# power_board.net
KiCad netlist of a schematic drawn in EAGLE
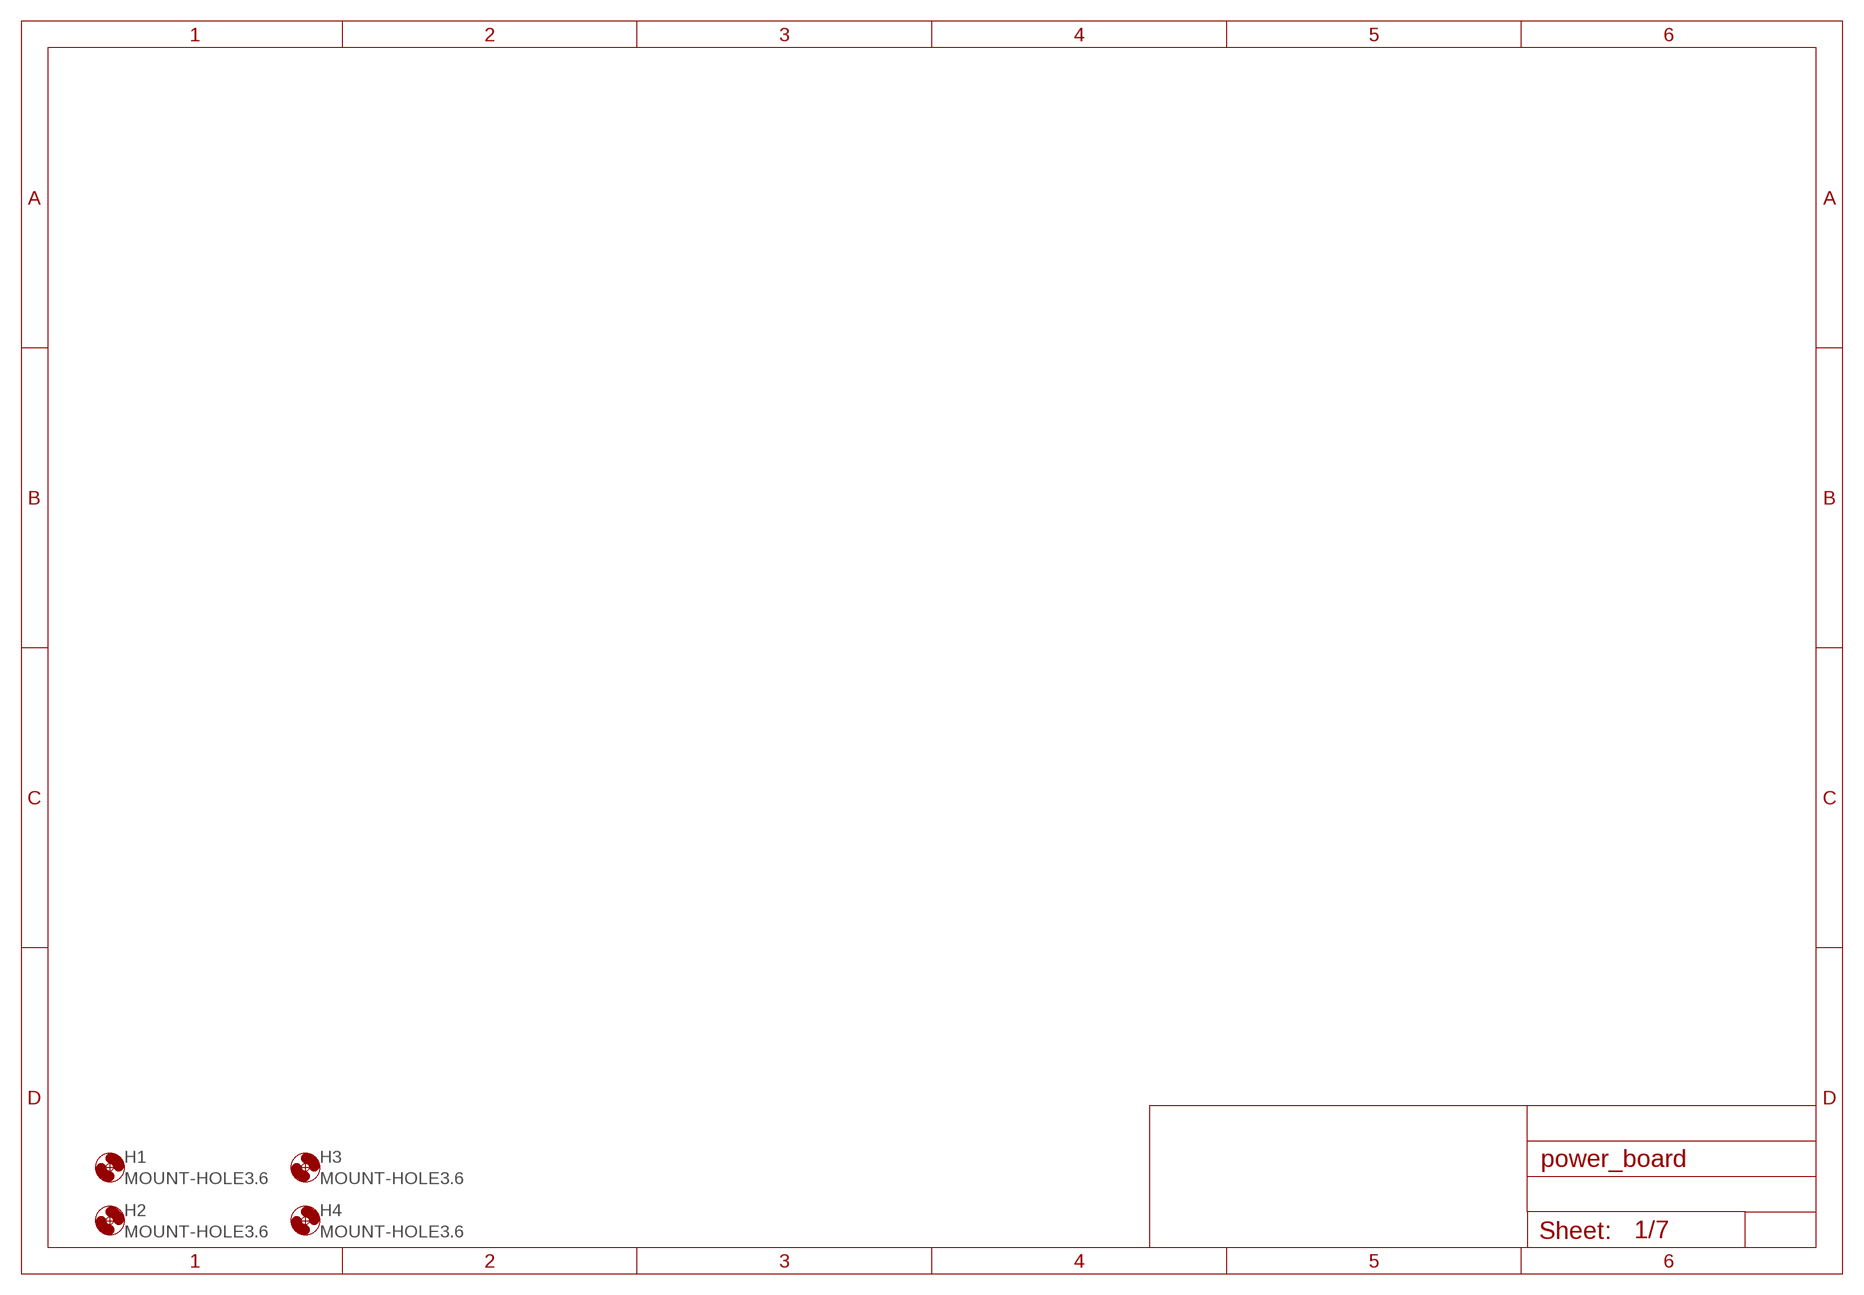
[diagram p0: schematic, sheet 1]
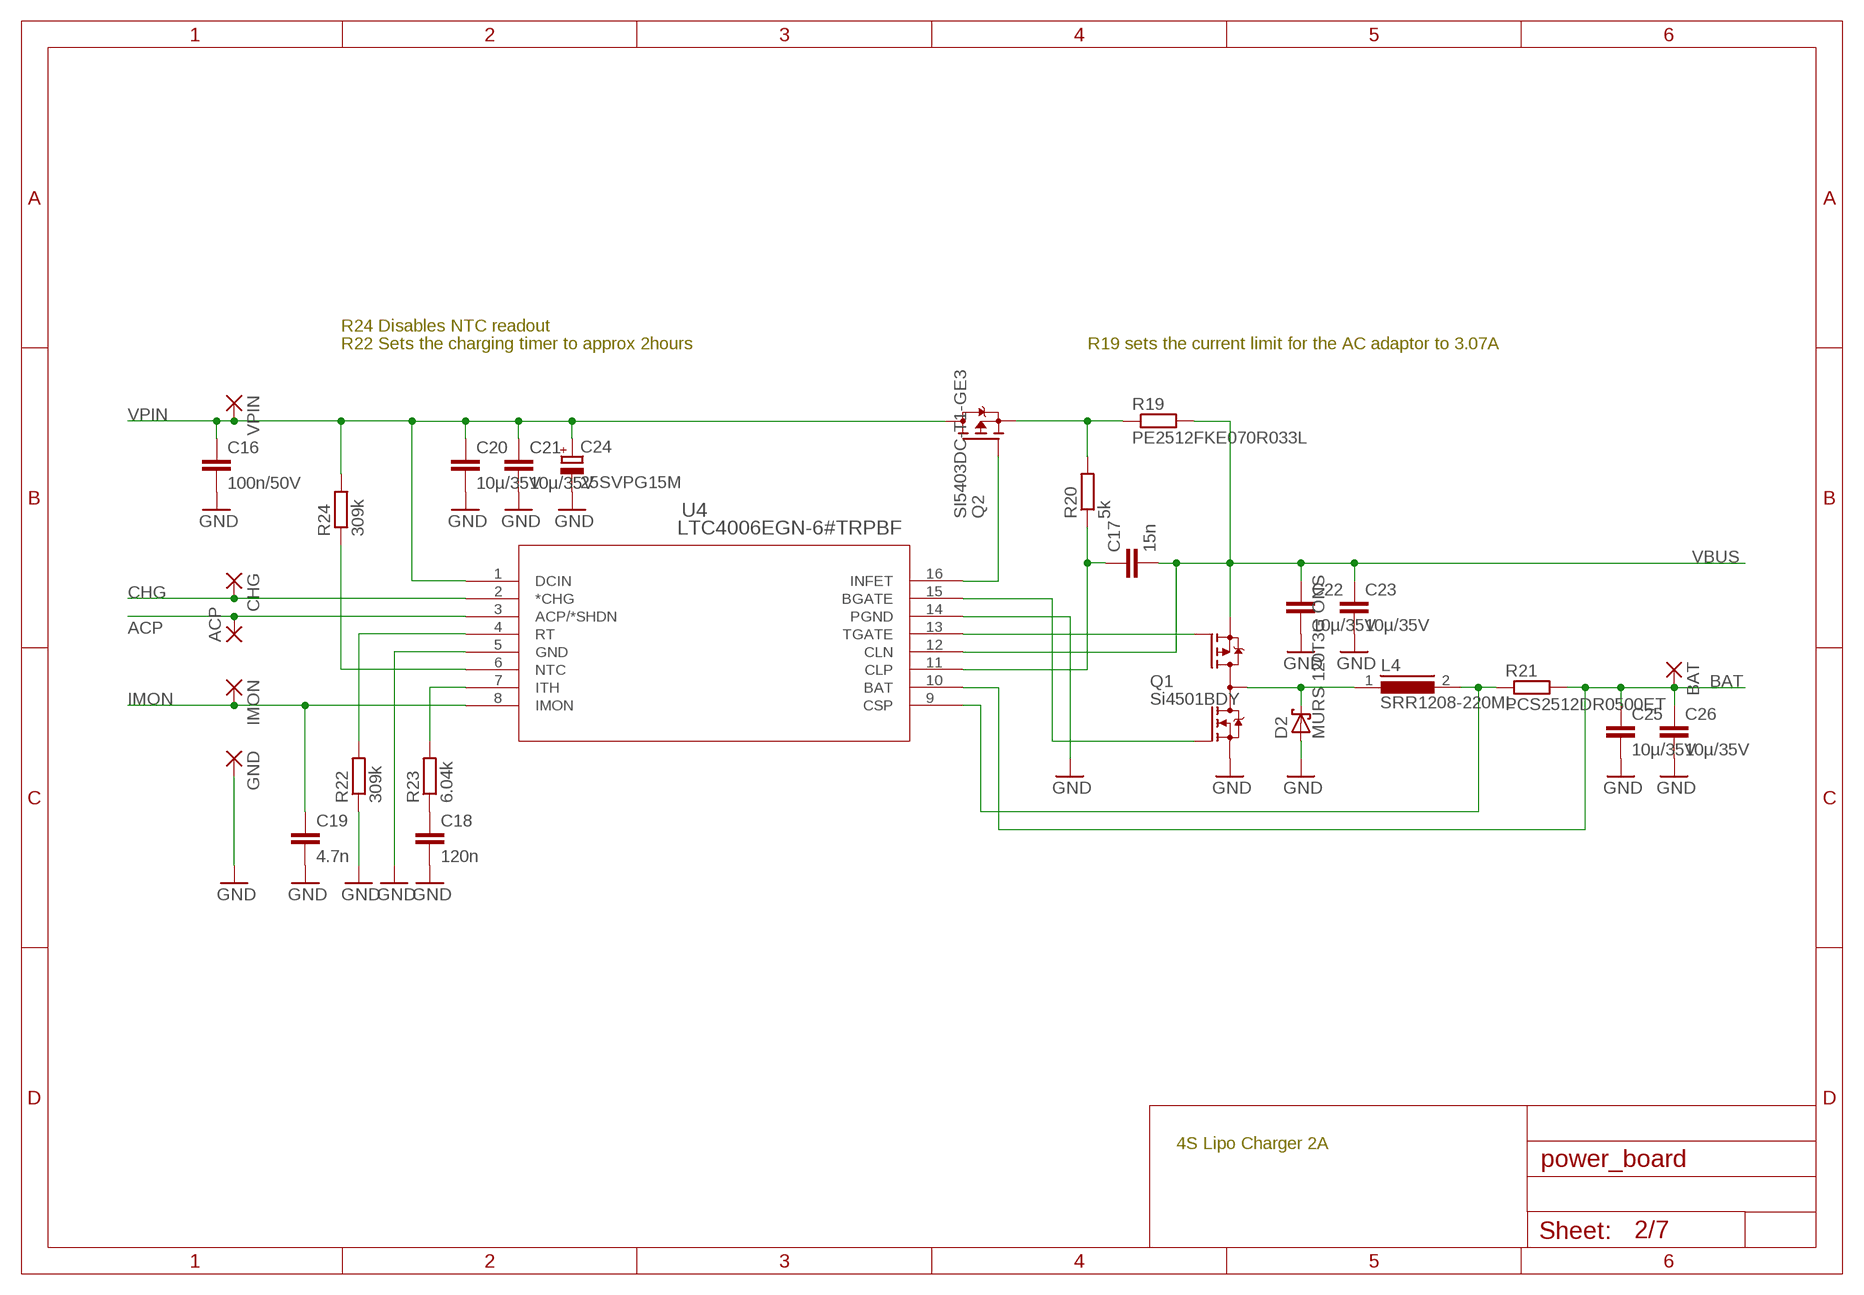
[diagram p1: schematic, sheet 2]
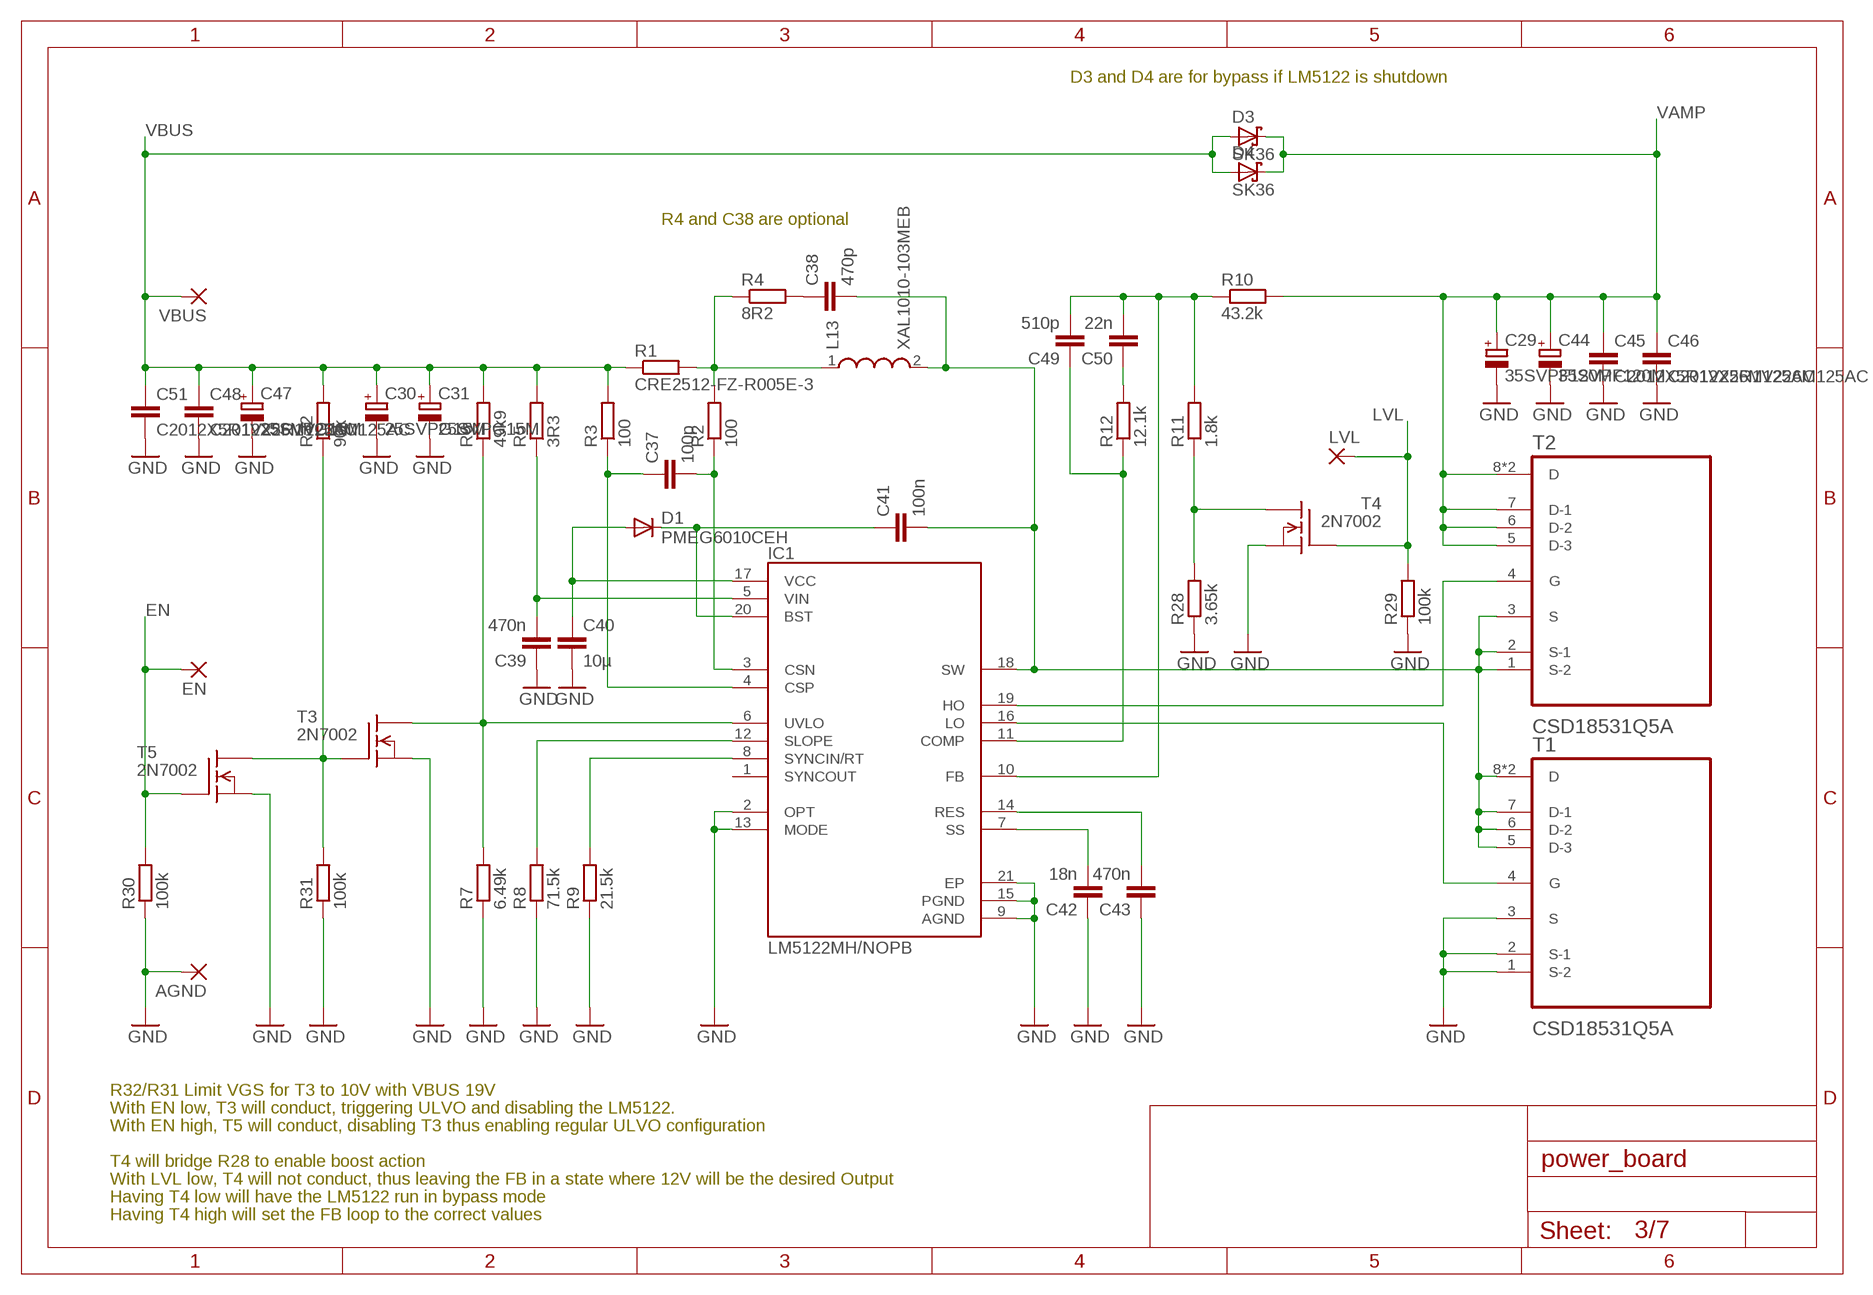
[diagram p2: schematic, sheet 3]
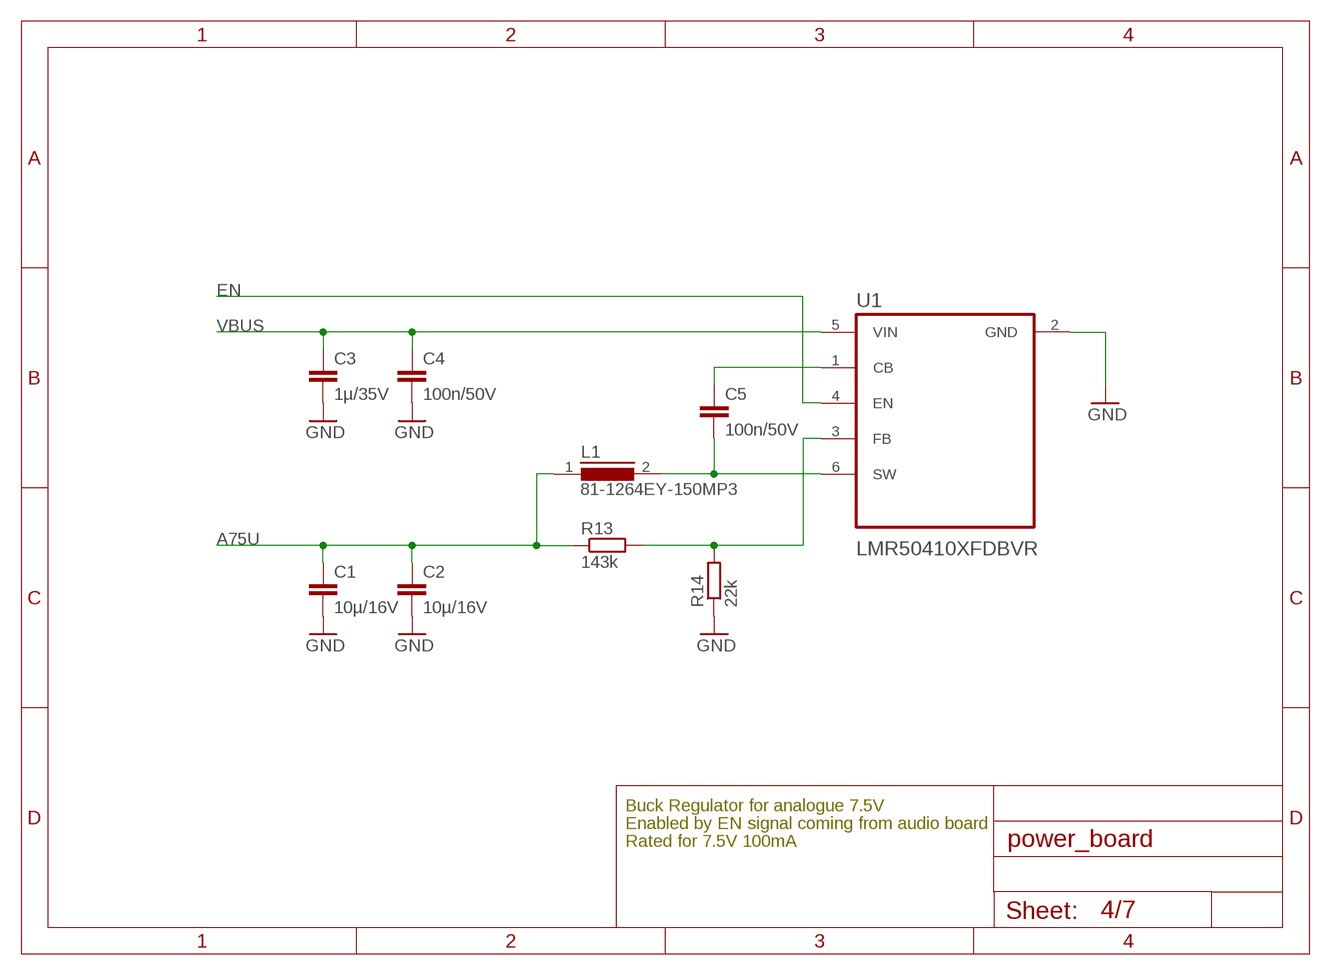
[diagram p3: schematic, sheet 4]
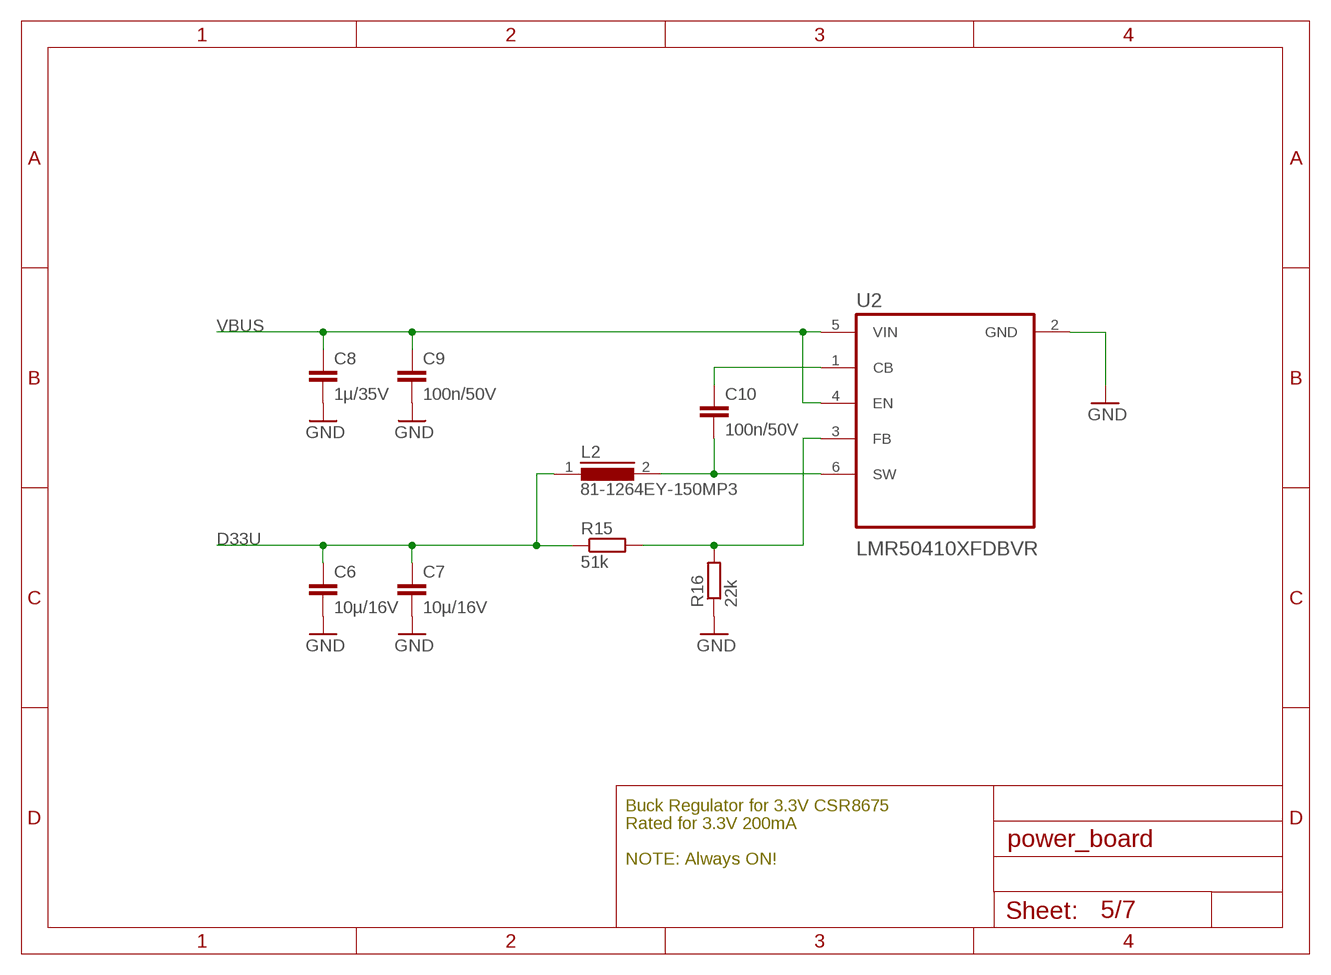
[diagram p4: schematic, sheet 5]
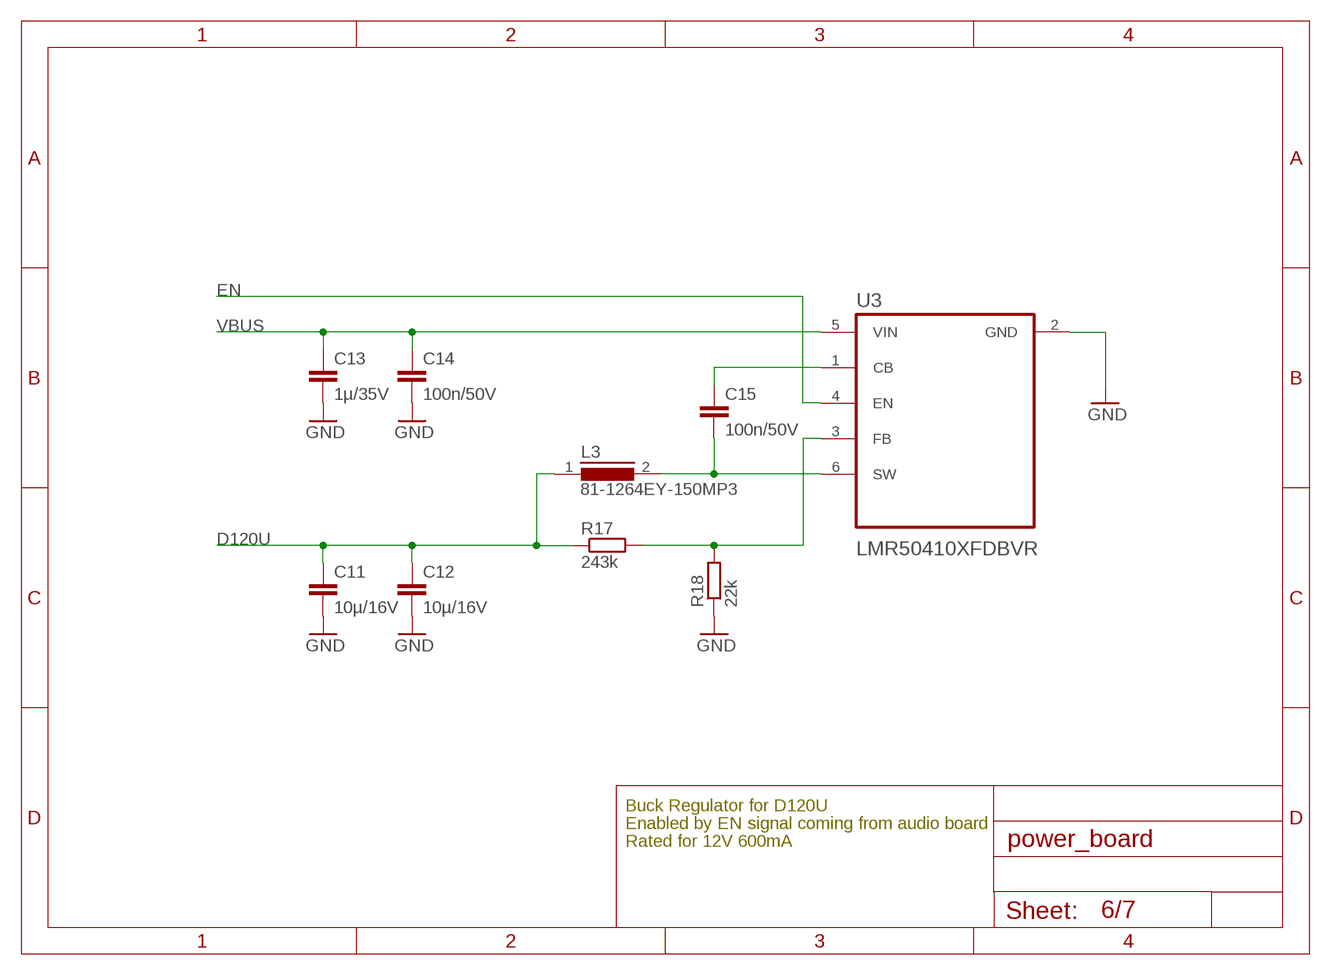
[diagram p5: schematic, sheet 6]
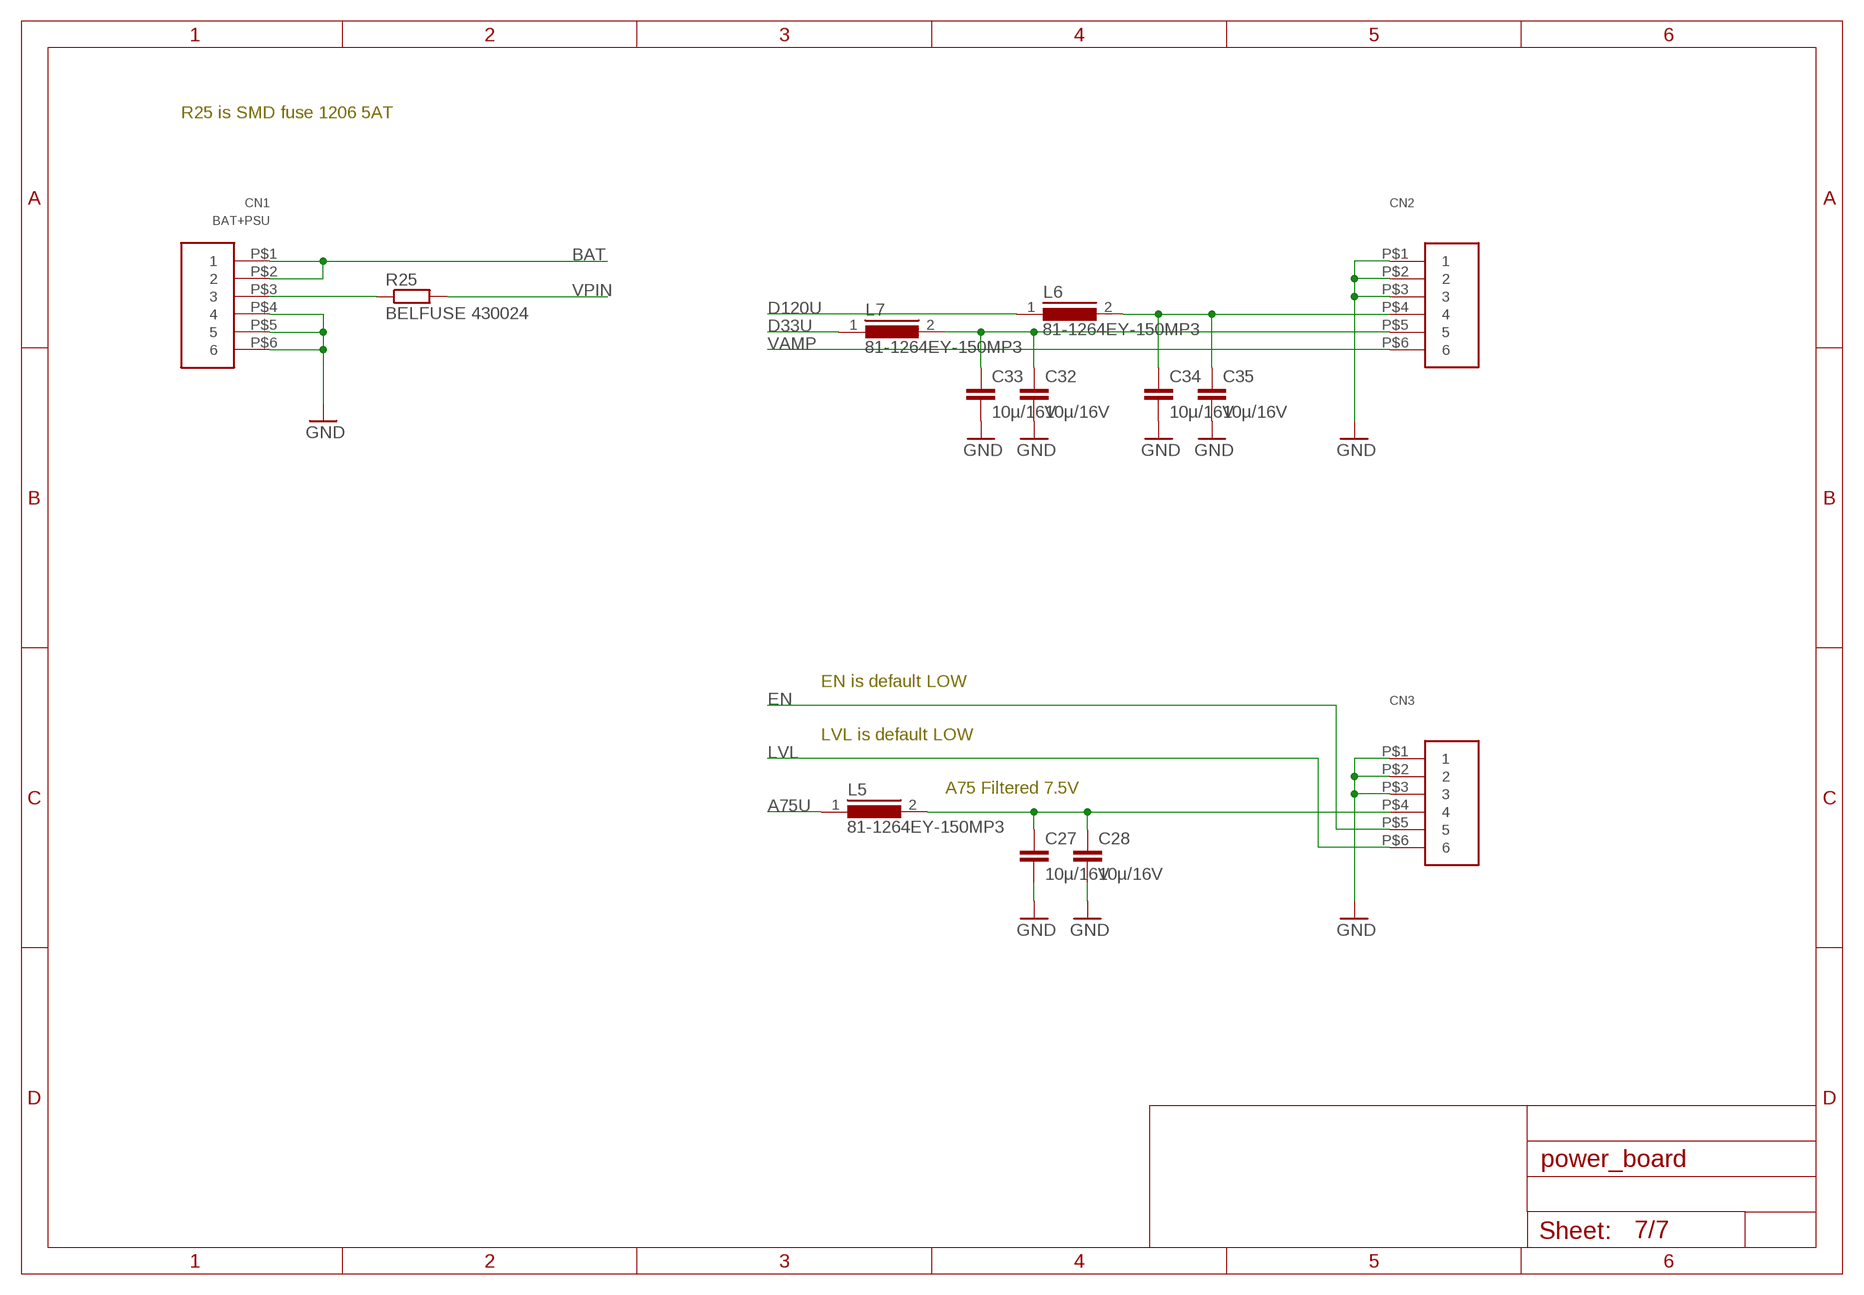
[diagram p6: schematic, sheet 7]

(export (version "E")
  (design (tool "Eeschema 10.0.6"))
  (components
    (comp (ref "H1")
      (value "MOUNT-HOLE3.6")
      (footprint "eagle-import:3,6")
      (libsource (lib "eagle-import") (part "MOUNT-HOLE3.6"))
    )
    (comp (ref "H2")
      (value "MOUNT-HOLE3.6")
      (footprint "eagle-import:3,6")
      (libsource (lib "eagle-import") (part "MOUNT-HOLE3.6"))
    )
    (comp (ref "H3")
      (value "MOUNT-HOLE3.6")
      (footprint "eagle-import:3,6")
      (libsource (lib "eagle-import") (part "MOUNT-HOLE3.6"))
    )
    (comp (ref "H4")
      (value "MOUNT-HOLE3.6")
      (footprint "eagle-import:3,6")
      (libsource (lib "eagle-import") (part "MOUNT-HOLE3.6"))
    )
    (comp (ref "C1")
      (value "10µ/16V")
      (footprint "eagle-import:C1206")
      (libsource (lib "eagle-import") (part "C-EUC1206"))
    )
    (comp (ref "C2")
      (value "10µ/16V")
      (footprint "eagle-import:C1206")
      (libsource (lib "eagle-import") (part "C-EUC1206"))
    )
    (comp (ref "C3")
      (value "1µ/35V")
      (footprint "eagle-import:C1206")
      (libsource (lib "eagle-import") (part "C-EUC1206"))
    )
    (comp (ref "C4")
      (value "100n/50V")
      (footprint "eagle-import:C1206")
      (libsource (lib "eagle-import") (part "C-EUC1206"))
    )
    (comp (ref "C5")
      (value "100n/50V")
      (footprint "eagle-import:C1206")
      (libsource (lib "eagle-import") (part "C-EUC1206"))
    )
    (comp (ref "L1")
      (value "81-1264EY-150MP3")
      (footprint "eagle-import:DR73")
      (libsource (lib "eagle-import") (part "DR73"))
    )
    (comp (ref "R13")
      (value "143k")
      (footprint "eagle-import:M0805")
      (libsource (lib "eagle-import") (part "R-EU_M0805"))
    )
    (comp (ref "R14")
      (value "22k")
      (footprint "eagle-import:M0805")
      (libsource (lib "eagle-import") (part "R-EU_M0805"))
    )
    (comp (ref "U1")
      (value "LMR50410XFDBVR")
      (footprint "eagle-import:SOT95P280X145-6N")
      (fields (field (name "MF") "Texas Instruments") (field (name "MP") "TPS560430YDBVT"))
      (libsource (lib "eagle-import") (part "TPS560430YDBVT"))
    )
    (comp (ref "C27")
      (value "10µ/16V")
      (footprint "eagle-import:C1206")
      (libsource (lib "eagle-import") (part "C-EUC1206"))
    )
    (comp (ref "C28")
      (value "10µ/16V")
      (footprint "eagle-import:C1206")
      (libsource (lib "eagle-import") (part "C-EUC1206"))
    )
    (comp (ref "C32")
      (value "10µ/16V")
      (footprint "eagle-import:C1206")
      (libsource (lib "eagle-import") (part "C-EUC1206"))
    )
    (comp (ref "C33")
      (value "10µ/16V")
      (footprint "eagle-import:C1206")
      (libsource (lib "eagle-import") (part "C-EUC1206"))
    )
    (comp (ref "C34")
      (value "10µ/16V")
      (footprint "eagle-import:C1206")
      (libsource (lib "eagle-import") (part "C-EUC1206"))
    )
    (comp (ref "C35")
      (value "10µ/16V")
      (footprint "eagle-import:C1206")
      (libsource (lib "eagle-import") (part "C-EUC1206"))
    )
    (comp (ref "CN1")
      (value "BAT+PSU")
      (footprint "eagle-import:5569_6P")
      (libsource (lib "eagle-import") (part "39-30-1060_BLANK"))
    )
    (comp (ref "CN2")
      (value "39-30-1060_BLANK")
      (footprint "eagle-import:5569_6P")
      (libsource (lib "eagle-import") (part "39-30-1060_BLANK"))
    )
    (comp (ref "CN3")
      (value "39-30-1060_BLANK")
      (footprint "eagle-import:5569_6P")
      (libsource (lib "eagle-import") (part "39-30-1060_BLANK"))
    )
    (comp (ref "L5")
      (value "81-1264EY-150MP3")
      (footprint "eagle-import:DR73")
      (libsource (lib "eagle-import") (part "DR73"))
    )
    (comp (ref "L6")
      (value "81-1264EY-150MP3")
      (footprint "eagle-import:DR73")
      (libsource (lib "eagle-import") (part "DR73"))
    )
    (comp (ref "L7")
      (value "81-1264EY-150MP3")
      (footprint "eagle-import:DR73")
      (libsource (lib "eagle-import") (part "DR73"))
    )
    (comp (ref "R25")
      (value "BELFUSE 430024")
      (footprint "eagle-import:R1206W")
      (libsource (lib "eagle-import") (part "R-EU_R1206W"))
    )
    (comp (ref "C6")
      (value "10µ/16V")
      (footprint "eagle-import:C1206")
      (libsource (lib "eagle-import") (part "C-EUC1206"))
    )
    (comp (ref "C7")
      (value "10µ/16V")
      (footprint "eagle-import:C1206")
      (libsource (lib "eagle-import") (part "C-EUC1206"))
    )
    (comp (ref "C8")
      (value "1µ/35V")
      (footprint "eagle-import:C1206")
      (libsource (lib "eagle-import") (part "C-EUC1206"))
    )
    (comp (ref "C9")
      (value "100n/50V")
      (footprint "eagle-import:C1206")
      (libsource (lib "eagle-import") (part "C-EUC1206"))
    )
    (comp (ref "C10")
      (value "100n/50V")
      (footprint "eagle-import:C1206")
      (libsource (lib "eagle-import") (part "C-EUC1206"))
    )
    (comp (ref "L2")
      (value "81-1264EY-150MP3")
      (footprint "eagle-import:DR73")
      (libsource (lib "eagle-import") (part "DR73"))
    )
    (comp (ref "R15")
      (value "51k")
      (footprint "eagle-import:M0805")
      (libsource (lib "eagle-import") (part "R-EU_M0805"))
    )
    (comp (ref "R16")
      (value "22k")
      (footprint "eagle-import:M0805")
      (libsource (lib "eagle-import") (part "R-EU_M0805"))
    )
    (comp (ref "U2")
      (value "LMR50410XFDBVR")
      (footprint "eagle-import:SOT95P280X145-6N")
      (fields (field (name "MF") "Texas Instruments") (field (name "MP") "TPS560430YDBVT"))
      (libsource (lib "eagle-import") (part "TPS560430YDBVT"))
    )
    (comp (ref "ACP")
      (value "SMD2")
      (footprint "eagle-import:SMD1,27-2,54")
      (libsource (lib "eagle-import") (part "SMD2"))
    )
    (comp (ref "BAT")
      (value "SMD2")
      (footprint "eagle-import:SMD1,27-2,54")
      (libsource (lib "eagle-import") (part "SMD2"))
    )
    (comp (ref "C16")
      (value "100n/50V")
      (footprint "eagle-import:C1206")
      (libsource (lib "eagle-import") (part "C-EUC1206"))
    )
    (comp (ref "C17")
      (value "15n")
      (footprint "eagle-import:C0805")
      (libsource (lib "eagle-import") (part "C-EUC0805"))
    )
    (comp (ref "C18")
      (value "120n")
      (footprint "eagle-import:C0805")
      (libsource (lib "eagle-import") (part "C-EUC0805"))
    )
    (comp (ref "C19")
      (value "4.7n")
      (footprint "eagle-import:C0805")
      (libsource (lib "eagle-import") (part "C-EUC0805"))
    )
    (comp (ref "C20")
      (value "10µ/35V")
      (footprint "eagle-import:C1206")
      (libsource (lib "eagle-import") (part "C-EUC1206"))
    )
    (comp (ref "C21")
      (value "10µ/35V")
      (footprint "eagle-import:C1206")
      (libsource (lib "eagle-import") (part "C-EUC1206"))
    )
    (comp (ref "C22")
      (value "10µ/35V")
      (footprint "eagle-import:C1206")
      (libsource (lib "eagle-import") (part "C-EUC1206"))
    )
    (comp (ref "C23")
      (value "10µ/35V")
      (footprint "eagle-import:C1206")
      (libsource (lib "eagle-import") (part "C-EUC1206"))
    )
    (comp (ref "C24")
      (value "25SVPG15M")
      (footprint "eagle-import:153CLV-0505")
      (libsource (lib "eagle-import") (part "CPOL-EU153CLV-0505"))
    )
    (comp (ref "C25")
      (value "10µ/35V")
      (footprint "eagle-import:C1206")
      (libsource (lib "eagle-import") (part "C-EUC1206"))
    )
    (comp (ref "C26")
      (value "10µ/35V")
      (footprint "eagle-import:C1206")
      (libsource (lib "eagle-import") (part "C-EUC1206"))
    )
    (comp (ref "CHG")
      (value "SMD2")
      (footprint "eagle-import:SMD1,27-2,54")
      (libsource (lib "eagle-import") (part "SMD2"))
    )
    (comp (ref "D2")
      (value "MURS 120T3G ONS")
      (footprint "eagle-import:SMB")
      (libsource (lib "eagle-import") (part "SCHOTTKY-DIODESMD"))
    )
    (comp (ref "GND")
      (value "SMD2")
      (footprint "eagle-import:SMD1,27-2,54")
      (libsource (lib "eagle-import") (part "SMD2"))
    )
    (comp (ref "IMON")
      (value "SMD2")
      (footprint "eagle-import:SMD1,27-2,54")
      (libsource (lib "eagle-import") (part "SMD2"))
    )
    (comp (ref "L4")
      (value "SRR1208-220ML")
      (footprint "eagle-import:DR127")
      (libsource (lib "eagle-import") (part "DR127"))
    )
    (comp (ref "Q1")
      (value "Si4501BDY")
      (footprint "eagle-import:SO08-IRF")
      (libsource (lib "eagle-import") (part "IRF7389"))
    )
    (comp (ref "Q2")
      (value "SI5403DC-T1-GE3")
      (footprint "eagle-import:1206-8CHIP-FET")
      (libsource (lib "eagle-import") (part "SI5403DC-T1-GE3"))
    )
    (comp (ref "R19")
      (value "PE2512FKE070R033L")
      (footprint "eagle-import:R2512")
      (libsource (lib "eagle-import") (part "R-EU_R2512"))
    )
    (comp (ref "R20")
      (value "5k")
      (footprint "eagle-import:R0805")
      (libsource (lib "eagle-import") (part "R-EU_R0805"))
    )
    (comp (ref "R21")
      (value "PCS2512DR0500ET")
      (footprint "eagle-import:R2512")
      (libsource (lib "eagle-import") (part "R-EU_R2512"))
    )
    (comp (ref "R22")
      (value "309k")
      (footprint "eagle-import:R0805")
      (libsource (lib "eagle-import") (part "R-EU_R0805"))
    )
    (comp (ref "R23")
      (value "6.04k")
      (footprint "eagle-import:R0805")
      (libsource (lib "eagle-import") (part "R-EU_R0805"))
    )
    (comp (ref "R24")
      (value "309k")
      (footprint "eagle-import:R0805")
      (libsource (lib "eagle-import") (part "R-EU_R0805"))
    )
    (comp (ref "U4")
      (value "LTC4006EGN-6#TRPBF")
      (footprint "eagle-import:SSOP-16_GN")
      (fields (field (name "MF") "Analog Devices"))
      (libsource (lib "eagle-import") (part "LTC4006EGN-6#TRPBF"))
    )
    (comp (ref "VPIN")
      (value "SMD2")
      (footprint "eagle-import:SMD1,27-2,54")
      (libsource (lib "eagle-import") (part "SMD2"))
    )
    (comp (ref "C11")
      (value "10µ/16V")
      (footprint "eagle-import:C1206")
      (libsource (lib "eagle-import") (part "C-EUC1206"))
    )
    (comp (ref "C12")
      (value "10µ/16V")
      (footprint "eagle-import:C1206")
      (libsource (lib "eagle-import") (part "C-EUC1206"))
    )
    (comp (ref "C13")
      (value "1µ/35V")
      (footprint "eagle-import:C1206")
      (libsource (lib "eagle-import") (part "C-EUC1206"))
    )
    (comp (ref "C14")
      (value "100n/50V")
      (footprint "eagle-import:C1206")
      (libsource (lib "eagle-import") (part "C-EUC1206"))
    )
    (comp (ref "C15")
      (value "100n/50V")
      (footprint "eagle-import:C1206")
      (libsource (lib "eagle-import") (part "C-EUC1206"))
    )
    (comp (ref "L3")
      (value "81-1264EY-150MP3")
      (footprint "eagle-import:DR73")
      (libsource (lib "eagle-import") (part "DR73"))
    )
    (comp (ref "R17")
      (value "243k")
      (footprint "eagle-import:M0805")
      (libsource (lib "eagle-import") (part "R-EU_M0805"))
    )
    (comp (ref "R18")
      (value "22k")
      (footprint "eagle-import:M0805")
      (libsource (lib "eagle-import") (part "R-EU_M0805"))
    )
    (comp (ref "U3")
      (value "LMR50410XFDBVR")
      (footprint "eagle-import:SOT95P280X145-6N")
      (fields (field (name "MF") "Texas Instruments") (field (name "MP") "TPS560430YDBVT"))
      (libsource (lib "eagle-import") (part "TPS560430YDBVT"))
    )
    (comp (ref "AGND")
      (value "SMD2")
      (footprint "eagle-import:SMD1,27-2,54")
      (libsource (lib "eagle-import") (part "SMD2"))
    )
    (comp (ref "C29")
      (value "35SVPF120M")
      (footprint "eagle-import:153CLV-1012")
      (libsource (lib "eagle-import") (part "CPOL-EU153CLV-1012"))
    )
    (comp (ref "C30")
      (value "25SVPG15M")
      (footprint "eagle-import:153CLV-0505")
      (libsource (lib "eagle-import") (part "CPOL-EU153CLV-0505"))
    )
    (comp (ref "C31")
      (value "25SVPG15M")
      (footprint "eagle-import:153CLV-0505")
      (libsource (lib "eagle-import") (part "CPOL-EU153CLV-0505"))
    )
    (comp (ref "C37")
      (value "100p")
      (footprint "eagle-import:C0805")
      (libsource (lib "eagle-import") (part "C-EUC0805"))
    )
    (comp (ref "C38")
      (value "470p")
      (footprint "eagle-import:C0805")
      (libsource (lib "eagle-import") (part "C-EUC0805"))
    )
    (comp (ref "C39")
      (value "470n")
      (footprint "eagle-import:C0805")
      (libsource (lib "eagle-import") (part "C-EUC0805"))
    )
    (comp (ref "C40")
      (value "10µ")
      (footprint "eagle-import:C1206")
      (libsource (lib "eagle-import") (part "C-EUC1206"))
    )
    (comp (ref "C41")
      (value "100n")
      (footprint "eagle-import:C0805")
      (libsource (lib "eagle-import") (part "C-EUC0805"))
    )
    (comp (ref "C42")
      (value "18n")
      (footprint "eagle-import:C0805")
      (libsource (lib "eagle-import") (part "C-EUC0805"))
    )
    (comp (ref "C43")
      (value "470n")
      (footprint "eagle-import:C0805")
      (libsource (lib "eagle-import") (part "C-EUC0805"))
    )
    (comp (ref "C44")
      (value "35SVPF120M")
      (footprint "eagle-import:153CLV-1012")
      (libsource (lib "eagle-import") (part "CPOL-EU153CLV-1012"))
    )
    (comp (ref "C45")
      (value "C2012X5R1V226M125AC")
      (footprint "eagle-import:C0805")
      (libsource (lib "eagle-import") (part "C-EUC0805"))
    )
    (comp (ref "C46")
      (value "C2012X5R1V226M125AC")
      (footprint "eagle-import:C0805")
      (libsource (lib "eagle-import") (part "C-EUC0805"))
    )
    (comp (ref "C47")
      (value "25SVPG15M")
      (footprint "eagle-import:153CLV-0505")
      (libsource (lib "eagle-import") (part "CPOL-EU153CLV-0505"))
    )
    (comp (ref "C48")
      (value "C2012X5R1V226M125AC")
      (footprint "eagle-import:C0805")
      (libsource (lib "eagle-import") (part "C-EUC0805"))
    )
    (comp (ref "C49")
      (value "510p")
      (footprint "eagle-import:C0805")
      (libsource (lib "eagle-import") (part "C-EUC0805"))
    )
    (comp (ref "C50")
      (value "22n")
      (footprint "eagle-import:C0805")
      (libsource (lib "eagle-import") (part "C-EUC0805"))
    )
    (comp (ref "C51")
      (value "C2012X5R1V226M125AC")
      (footprint "eagle-import:C0805")
      (libsource (lib "eagle-import") (part "C-EUC0805"))
    )
    (comp (ref "D1")
      (value "PMEG6010CEH")
      (footprint "eagle-import:SOD323-W")
      (libsource (lib "eagle-import") (part "DIODE-SOD323-W"))
    )
    (comp (ref "D3")
      (value "SK36")
      (footprint "eagle-import:SMB")
      (libsource (lib "eagle-import") (part "SCHOTTKY-DIODESMD"))
    )
    (comp (ref "D4")
      (value "SK36")
      (footprint "eagle-import:SMB")
      (libsource (lib "eagle-import") (part "SCHOTTKY-DIODESMD"))
    )
    (comp (ref "EN")
      (value "SMD2")
      (footprint "eagle-import:SMD1,27-2,54")
      (libsource (lib "eagle-import") (part "SMD2"))
    )
    (comp (ref "IC1")
      (value "LM5122MH/NOPB")
      (footprint "eagle-import:SOP65P640X110-21N")
      (fields (field (name "MF") "Texas Instruments"))
      (libsource (lib "eagle-import") (part "LM5122MH/NOPB"))
    )
    (comp (ref "L13")
      (value "XAL1010-103MEB")
      (footprint "eagle-import:INDC110100X1000N")
      (fields (field (name "MF") "Coilcraft") (field (name "MP") "XAL1010-472MED"))
      (libsource (lib "eagle-import") (part "XAL1010-472MED"))
    )
    (comp (ref "LVL")
      (value "SMD2")
      (footprint "eagle-import:SMD1,27-2,54")
      (libsource (lib "eagle-import") (part "SMD2"))
    )
    (comp (ref "R1")
      (value "CRE2512-FZ-R005E-3")
      (footprint "eagle-import:R2512")
      (libsource (lib "eagle-import") (part "R-EU_R2512"))
    )
    (comp (ref "R2")
      (value "100")
      (footprint "eagle-import:R0805")
      (libsource (lib "eagle-import") (part "R-EU_R0805"))
    )
    (comp (ref "R3")
      (value "100")
      (footprint "eagle-import:R0805")
      (libsource (lib "eagle-import") (part "R-EU_R0805"))
    )
    (comp (ref "R4")
      (value "8R2")
      (footprint "eagle-import:M0805")
      (libsource (lib "eagle-import") (part "R-EU_M0805"))
    )
    (comp (ref "R5")
      (value "3R3")
      (footprint "eagle-import:R0805")
      (libsource (lib "eagle-import") (part "R-EU_R0805"))
    )
    (comp (ref "R6")
      (value "49k9")
      (footprint "eagle-import:R0805")
      (libsource (lib "eagle-import") (part "R-EU_R0805"))
    )
    (comp (ref "R7")
      (value "6.49k")
      (footprint "eagle-import:R0805")
      (libsource (lib "eagle-import") (part "R-EU_R0805"))
    )
    (comp (ref "R8")
      (value "71.5k")
      (footprint "eagle-import:R0805")
      (libsource (lib "eagle-import") (part "R-EU_R0805"))
    )
    (comp (ref "R9")
      (value "21.5k")
      (footprint "eagle-import:R0805")
      (libsource (lib "eagle-import") (part "R-EU_R0805"))
    )
    (comp (ref "R10")
      (value "43.2k")
      (footprint "eagle-import:R0805")
      (libsource (lib "eagle-import") (part "R-EU_R0805"))
    )
    (comp (ref "R11")
      (value "1.8k")
      (footprint "eagle-import:R0805")
      (libsource (lib "eagle-import") (part "R-EU_R0805"))
    )
    (comp (ref "R12")
      (value "12.1k")
      (footprint "eagle-import:R0805")
      (libsource (lib "eagle-import") (part "R-EU_R0805"))
    )
    (comp (ref "R28")
      (value "3.65k")
      (footprint "eagle-import:R0805")
      (libsource (lib "eagle-import") (part "R-EU_R0805"))
    )
    (comp (ref "R29")
      (value "100k")
      (footprint "eagle-import:R0805")
      (libsource (lib "eagle-import") (part "R-EU_R0805"))
    )
    (comp (ref "R30")
      (value "100k")
      (footprint "eagle-import:R0805")
      (libsource (lib "eagle-import") (part "R-EU_R0805"))
    )
    (comp (ref "R31")
      (value "100k")
      (footprint "eagle-import:R0805")
      (libsource (lib "eagle-import") (part "R-EU_R0805"))
    )
    (comp (ref "R32")
      (value "90k")
      (footprint "eagle-import:R0805")
      (libsource (lib "eagle-import") (part "R-EU_R0805"))
    )
    (comp (ref "T1")
      (value "CSD18531Q5A")
      (footprint "eagle-import:MOSFET_CSD19531Q5A")
      (fields (field (name "MF") "Texas Instruments"))
      (libsource (lib "eagle-import") (part "CSD18531Q5A"))
    )
    (comp (ref "T2")
      (value "CSD18531Q5A")
      (footprint "eagle-import:MOSFET_CSD19531Q5A")
      (fields (field (name "MF") "Texas Instruments"))
      (libsource (lib "eagle-import") (part "CSD18531Q5A"))
    )
    (comp (ref "T3")
      (value "2N7002")
      (footprint "eagle-import:SOT23")
      (libsource (lib "eagle-import") (part "2N7002"))
    )
    (comp (ref "T4")
      (value "2N7002")
      (footprint "eagle-import:SOT23")
      (libsource (lib "eagle-import") (part "2N7002"))
    )
    (comp (ref "T5")
      (value "2N7002")
      (footprint "eagle-import:SOT23")
      (libsource (lib "eagle-import") (part "2N7002"))
    )
    (comp (ref "VBUS")
      (value "SMD2")
      (footprint "eagle-import:SMD1,27-2,54")
      (libsource (lib "eagle-import") (part "SMD2"))
    )
  )
  (nets
    (net (code "1") (name "A75U") (class "Default")
      (node (ref "C1") (pin "1") (pinfunction "1_1") (pintype "passive"))
      (node (ref "C2") (pin "1") (pinfunction "1_1") (pintype "passive"))
      (node (ref "L1") (pin "1") (pinfunction "1_1") (pintype "passive"))
      (node (ref "L5") (pin "1") (pinfunction "1_1") (pintype "passive"))
      (node (ref "R13") (pin "1") (pinfunction "1_1") (pintype "passive"))
    )
    (net (code "2") (name "ACP") (class "Default")
      (node (ref "ACP") (pin "1") (pinfunction "P_1") (pintype "passive"))
      (node (ref "U4") (pin "3") (pinfunction "ACP/*SHDN_3") (pintype "output"))
    )
    (net (code "3") (name "BAT") (class "Default")
      (node (ref "BAT") (pin "1") (pinfunction "P_1") (pintype "passive"))
      (node (ref "C25") (pin "1") (pinfunction "1_1") (pintype "passive"))
      (node (ref "C26") (pin "1") (pinfunction "1_1") (pintype "passive"))
      (node (ref "CN1") (pin "P$1") (pinfunction "1_P$1") (pintype "bidirectional"))
      (node (ref "CN1") (pin "P$2") (pinfunction "2_P$2") (pintype "bidirectional"))
      (node (ref "R21") (pin "2") (pinfunction "2_2") (pintype "passive"))
      (node (ref "U4") (pin "10") (pinfunction "BAT_10") (pintype "input"))
    )
    (net (code "4") (name "CHG") (class "Default")
      (node (ref "CHG") (pin "1") (pinfunction "P_1") (pintype "passive"))
      (node (ref "U4") (pin "2") (pinfunction "*CHG_2") (pintype "output"))
    )
    (net (code "5") (name "D33U") (class "Default")
      (node (ref "C6") (pin "1") (pinfunction "1_1") (pintype "passive"))
      (node (ref "C7") (pin "1") (pinfunction "1_1") (pintype "passive"))
      (node (ref "L2") (pin "1") (pinfunction "1_1") (pintype "passive"))
      (node (ref "L7") (pin "1") (pinfunction "1_1") (pintype "passive"))
      (node (ref "R15") (pin "1") (pinfunction "1_1") (pintype "passive"))
    )
    (net (code "6") (name "D120U") (class "Default")
      (node (ref "C11") (pin "1") (pinfunction "1_1") (pintype "passive"))
      (node (ref "C12") (pin "1") (pinfunction "1_1") (pintype "passive"))
      (node (ref "L3") (pin "1") (pinfunction "1_1") (pintype "passive"))
      (node (ref "L6") (pin "1") (pinfunction "1_1") (pintype "passive"))
      (node (ref "R17") (pin "1") (pinfunction "1_1") (pintype "passive"))
    )
    (net (code "7") (name "EN") (class "Default")
      (node (ref "CN3") (pin "P$5") (pinfunction "5_P$5") (pintype "bidirectional"))
      (node (ref "EN") (pin "1") (pinfunction "P_1") (pintype "passive"))
      (node (ref "R30") (pin "2") (pinfunction "2_2") (pintype "passive"))
      (node (ref "T5") (pin "1") (pinfunction "G_1") (pintype "passive"))
      (node (ref "U1") (pin "4") (pinfunction "EN_4") (pintype "bidirectional"))
      (node (ref "U3") (pin "4") (pinfunction "EN_4") (pintype "bidirectional"))
    )
    (net (code "8") (name "GND") (class "Default")
      (node (ref "AGND") (pin "1") (pinfunction "P_1") (pintype "passive"))
      (node (ref "C1") (pin "2") (pinfunction "2_2") (pintype "passive"))
      (node (ref "C11") (pin "2") (pinfunction "2_2") (pintype "passive"))
      (node (ref "C12") (pin "2") (pinfunction "2_2") (pintype "passive"))
      (node (ref "C13") (pin "2") (pinfunction "2_2") (pintype "passive"))
      (node (ref "C14") (pin "2") (pinfunction "2_2") (pintype "passive"))
      (node (ref "C16") (pin "2") (pinfunction "2_2") (pintype "passive"))
      (node (ref "C18") (pin "2") (pinfunction "2_2") (pintype "passive"))
      (node (ref "C19") (pin "2") (pinfunction "2_2") (pintype "passive"))
      (node (ref "C2") (pin "2") (pinfunction "2_2") (pintype "passive"))
      (node (ref "C20") (pin "2") (pinfunction "2_2") (pintype "passive"))
      (node (ref "C21") (pin "2") (pinfunction "2_2") (pintype "passive"))
      (node (ref "C22") (pin "2") (pinfunction "2_2") (pintype "passive"))
      (node (ref "C23") (pin "2") (pinfunction "2_2") (pintype "passive"))
      (node (ref "C24") (pin "-") (pinfunction "-_-") (pintype "passive"))
      (node (ref "C25") (pin "2") (pinfunction "2_2") (pintype "passive"))
      (node (ref "C26") (pin "2") (pinfunction "2_2") (pintype "passive"))
      (node (ref "C27") (pin "2") (pinfunction "2_2") (pintype "passive"))
      (node (ref "C28") (pin "2") (pinfunction "2_2") (pintype "passive"))
      (node (ref "C29") (pin "-") (pinfunction "-_-") (pintype "passive"))
      (node (ref "C3") (pin "2") (pinfunction "2_2") (pintype "passive"))
      (node (ref "C30") (pin "-") (pinfunction "-_-") (pintype "passive"))
      (node (ref "C31") (pin "-") (pinfunction "-_-") (pintype "passive"))
      (node (ref "C32") (pin "2") (pinfunction "2_2") (pintype "passive"))
      (node (ref "C33") (pin "2") (pinfunction "2_2") (pintype "passive"))
      (node (ref "C34") (pin "2") (pinfunction "2_2") (pintype "passive"))
      (node (ref "C35") (pin "2") (pinfunction "2_2") (pintype "passive"))
      (node (ref "C39") (pin "1") (pinfunction "1_1") (pintype "passive"))
      (node (ref "C4") (pin "2") (pinfunction "2_2") (pintype "passive"))
      (node (ref "C40") (pin "2") (pinfunction "2_2") (pintype "passive"))
      (node (ref "C42") (pin "1") (pinfunction "1_1") (pintype "passive"))
      (node (ref "C43") (pin "1") (pinfunction "1_1") (pintype "passive"))
      (node (ref "C44") (pin "-") (pinfunction "-_-") (pintype "passive"))
      (node (ref "C45") (pin "2") (pinfunction "2_2") (pintype "passive"))
      (node (ref "C46") (pin "2") (pinfunction "2_2") (pintype "passive"))
      (node (ref "C47") (pin "-") (pinfunction "-_-") (pintype "passive"))
      (node (ref "C48") (pin "2") (pinfunction "2_2") (pintype "passive"))
      (node (ref "C51") (pin "2") (pinfunction "2_2") (pintype "passive"))
      (node (ref "C6") (pin "2") (pinfunction "2_2") (pintype "passive"))
      (node (ref "C7") (pin "2") (pinfunction "2_2") (pintype "passive"))
      (node (ref "C8") (pin "2") (pinfunction "2_2") (pintype "passive"))
      (node (ref "C9") (pin "2") (pinfunction "2_2") (pintype "passive"))
      (node (ref "CN1") (pin "P$4") (pinfunction "4_P$4") (pintype "bidirectional"))
      (node (ref "CN1") (pin "P$5") (pinfunction "5_P$5") (pintype "bidirectional"))
      (node (ref "CN1") (pin "P$6") (pinfunction "6_P$6") (pintype "bidirectional"))
      (node (ref "CN2") (pin "P$1") (pinfunction "1_P$1") (pintype "bidirectional"))
      (node (ref "CN2") (pin "P$2") (pinfunction "2_P$2") (pintype "bidirectional"))
      (node (ref "CN2") (pin "P$3") (pinfunction "3_P$3") (pintype "bidirectional"))
      (node (ref "CN3") (pin "P$1") (pinfunction "1_P$1") (pintype "bidirectional"))
      (node (ref "CN3") (pin "P$2") (pinfunction "2_P$2") (pintype "bidirectional"))
      (node (ref "CN3") (pin "P$3") (pinfunction "3_P$3") (pintype "bidirectional"))
      (node (ref "D2") (pin "A") (pinfunction "A_A") (pintype "passive"))
      (node (ref "GND") (pin "1") (pinfunction "P_1") (pintype "passive"))
      (node (ref "IC1") (pin "13") (pinfunction "MODE_13") (pintype "input"))
      (node (ref "IC1") (pin "15") (pinfunction "PGND_15") (pintype "power_in"))
      (node (ref "IC1") (pin "2") (pinfunction "OPT_2") (pintype "input"))
      (node (ref "IC1") (pin "21") (pinfunction "EP_21") (pintype "passive"))
      (node (ref "IC1") (pin "9") (pinfunction "AGND_9") (pintype "power_in"))
      (node (ref "Q1") (pin "1") (pinfunction "N-S_1") (pintype "passive"))
      (node (ref "R14") (pin "1") (pinfunction "1_1") (pintype "passive"))
      (node (ref "R16") (pin "1") (pinfunction "1_1") (pintype "passive"))
      (node (ref "R18") (pin "1") (pinfunction "1_1") (pintype "passive"))
      (node (ref "R22") (pin "1") (pinfunction "1_1") (pintype "passive"))
      (node (ref "R28") (pin "1") (pinfunction "1_1") (pintype "passive"))
      (node (ref "R29") (pin "1") (pinfunction "1_1") (pintype "passive"))
      (node (ref "R30") (pin "1") (pinfunction "1_1") (pintype "passive"))
      (node (ref "R31") (pin "1") (pinfunction "1_1") (pintype "passive"))
      (node (ref "R7") (pin "1") (pinfunction "1_1") (pintype "passive"))
      (node (ref "R8") (pin "1") (pinfunction "1_1") (pintype "passive"))
      (node (ref "R9") (pin "1") (pinfunction "1_1") (pintype "passive"))
      (node (ref "T1") (pin "1") (pinfunction "S-2_1") (pintype "bidirectional"))
      (node (ref "T1") (pin "2") (pinfunction "S-1_2") (pintype "bidirectional"))
      (node (ref "T1") (pin "3") (pinfunction "S_3") (pintype "bidirectional"))
      (node (ref "T3") (pin "2") (pinfunction "S_2") (pintype "passive"))
      (node (ref "T4") (pin "2") (pinfunction "S_2") (pintype "passive"))
      (node (ref "T5") (pin "2") (pinfunction "S_2") (pintype "passive"))
      (node (ref "U1") (pin "2") (pinfunction "GND_2") (pintype "power_in"))
      (node (ref "U2") (pin "2") (pinfunction "GND_2") (pintype "power_in"))
      (node (ref "U3") (pin "2") (pinfunction "GND_2") (pintype "power_in"))
      (node (ref "U4") (pin "14") (pinfunction "PGND_14") (pintype "power_in"))
      (node (ref "U4") (pin "5") (pinfunction "GND_5") (pintype "power_in"))
    )
    (net (code "9") (name "IMON") (class "Default")
      (node (ref "C19") (pin "1") (pinfunction "1_1") (pintype "passive"))
      (node (ref "IMON") (pin "1") (pinfunction "P_1") (pintype "passive"))
      (node (ref "U4") (pin "8") (pinfunction "IMON_8") (pintype "output"))
    )
    (net (code "10") (name "LVL") (class "Default")
      (node (ref "CN3") (pin "P$6") (pinfunction "6_P$6") (pintype "bidirectional"))
      (node (ref "LVL") (pin "1") (pinfunction "P_1") (pintype "passive"))
      (node (ref "R29") (pin "2") (pinfunction "2_2") (pintype "passive"))
      (node (ref "T4") (pin "1") (pinfunction "G_1") (pintype "passive"))
    )
    (net (code "11") (name "Net-(C18-Pad1)") (class "Default")
      (node (ref "C18") (pin "1") (pinfunction "1_1") (pintype "passive"))
      (node (ref "R23") (pin "1") (pinfunction "1_1") (pintype "passive"))
    )
    (net (code "12") (name "Net-(C38-Pad1)") (class "Default")
      (node (ref "C38") (pin "1") (pinfunction "1_1") (pintype "passive"))
      (node (ref "R4") (pin "2") (pinfunction "2_2") (pintype "passive"))
    )
    (net (code "13") (name "Net-(C50-Pad1)") (class "Default")
      (node (ref "C50") (pin "1") (pinfunction "1_1") (pintype "passive"))
      (node (ref "R12") (pin "2") (pinfunction "2_2") (pintype "passive"))
    )
    (net (code "14") (name "Net-(CN1-3)") (class "Default")
      (node (ref "CN1") (pin "P$3") (pinfunction "3_P$3") (pintype "bidirectional"))
      (node (ref "R25") (pin "1") (pinfunction "1_1") (pintype "passive"))
    )
    (net (code "15") (name "Net-(CN2-4)") (class "Default")
      (node (ref "C34") (pin "1") (pinfunction "1_1") (pintype "passive"))
      (node (ref "C35") (pin "1") (pinfunction "1_1") (pintype "passive"))
      (node (ref "CN2") (pin "P$4") (pinfunction "4_P$4") (pintype "bidirectional"))
      (node (ref "L6") (pin "2") (pinfunction "2_2") (pintype "passive"))
    )
    (net (code "16") (name "Net-(CN2-5)") (class "Default")
      (node (ref "C32") (pin "1") (pinfunction "1_1") (pintype "passive"))
      (node (ref "C33") (pin "1") (pinfunction "1_1") (pintype "passive"))
      (node (ref "CN2") (pin "P$5") (pinfunction "5_P$5") (pintype "bidirectional"))
      (node (ref "L7") (pin "2") (pinfunction "2_2") (pintype "passive"))
    )
    (net (code "17") (name "Net-(CN3-4)") (class "Default")
      (node (ref "C27") (pin "1") (pinfunction "1_1") (pintype "passive"))
      (node (ref "C28") (pin "1") (pinfunction "1_1") (pintype "passive"))
      (node (ref "CN3") (pin "P$4") (pinfunction "4_P$4") (pintype "bidirectional"))
      (node (ref "L5") (pin "2") (pinfunction "2_2") (pintype "passive"))
    )
    (net (code "18") (name "Net-(D2-PadC)") (class "Default")
      (node (ref "D2") (pin "C") (pinfunction "C_C") (pintype "passive"))
      (node (ref "L4") (pin "1") (pinfunction "1_1") (pintype "passive"))
      (node (ref "Q1") (pin "5") (pinfunction "D_5") (pintype "passive"))
      (node (ref "Q1") (pin "6") (pinfunction "D_6") (pintype "passive"))
      (node (ref "Q1") (pin "7") (pinfunction "D_7") (pintype "passive"))
      (node (ref "Q1") (pin "8") (pinfunction "D_8") (pintype "passive"))
    )
    (net (code "19") (name "Net-(IC1-BST)") (class "Default")
      (node (ref "C41") (pin "1") (pinfunction "1_1") (pintype "passive"))
      (node (ref "D1") (pin "C") (pinfunction "C_C") (pintype "passive"))
      (node (ref "IC1") (pin "20") (pinfunction "BST_20") (pintype "power_in"))
    )
    (net (code "20") (name "Net-(IC1-COMP)") (class "Default")
      (node (ref "C49") (pin "1") (pinfunction "1_1") (pintype "passive"))
      (node (ref "IC1") (pin "11") (pinfunction "COMP_11") (pintype "output"))
      (node (ref "R12") (pin "1") (pinfunction "1_1") (pintype "passive"))
    )
    (net (code "21") (name "Net-(IC1-CSN)") (class "Default")
      (node (ref "C37") (pin "2") (pinfunction "2_2") (pintype "passive"))
      (node (ref "IC1") (pin "3") (pinfunction "CSN_3") (pintype "input"))
      (node (ref "R2") (pin "1") (pinfunction "1_1") (pintype "passive"))
    )
    (net (code "22") (name "Net-(IC1-CSP)") (class "Default")
      (node (ref "C37") (pin "1") (pinfunction "1_1") (pintype "passive"))
      (node (ref "IC1") (pin "4") (pinfunction "CSP_4") (pintype "input"))
      (node (ref "R3") (pin "1") (pinfunction "1_1") (pintype "passive"))
    )
    (net (code "23") (name "Net-(IC1-FB)") (class "Default")
      (node (ref "C49") (pin "2") (pinfunction "2_2") (pintype "passive"))
      (node (ref "C50") (pin "2") (pinfunction "2_2") (pintype "passive"))
      (node (ref "IC1") (pin "10") (pinfunction "FB_10") (pintype "input"))
      (node (ref "R10") (pin "1") (pinfunction "1_1") (pintype "passive"))
      (node (ref "R11") (pin "2") (pinfunction "2_2") (pintype "passive"))
    )
    (net (code "24") (name "Net-(IC1-HO)") (class "Default")
      (node (ref "IC1") (pin "19") (pinfunction "HO_19") (pintype "output"))
      (node (ref "T2") (pin "4") (pinfunction "G_4") (pintype "bidirectional"))
    )
    (net (code "25") (name "Net-(IC1-LO)") (class "Default")
      (node (ref "IC1") (pin "16") (pinfunction "LO_16") (pintype "output"))
      (node (ref "T1") (pin "4") (pinfunction "G_4") (pintype "bidirectional"))
    )
    (net (code "26") (name "Net-(IC1-RES)") (class "Default")
      (node (ref "C43") (pin "2") (pinfunction "2_2") (pintype "passive"))
      (node (ref "IC1") (pin "14") (pinfunction "RES_14") (pintype "output"))
    )
    (net (code "27") (name "Net-(IC1-SLOPE)") (class "Default")
      (node (ref "IC1") (pin "12") (pinfunction "SLOPE_12") (pintype "input"))
      (node (ref "R8") (pin "2") (pinfunction "2_2") (pintype "passive"))
    )
    (net (code "28") (name "Net-(IC1-SS)") (class "Default")
      (node (ref "C42") (pin "2") (pinfunction "2_2") (pintype "passive"))
      (node (ref "IC1") (pin "7") (pinfunction "SS_7") (pintype "input"))
    )
    (net (code "29") (name "Net-(IC1-SW)") (class "Default")
      (node (ref "C38") (pin "2") (pinfunction "2_2") (pintype "passive"))
      (node (ref "C41") (pin "2") (pinfunction "2_2") (pintype "passive"))
      (node (ref "IC1") (pin "18") (pinfunction "SW_18") (pintype "bidirectional"))
      (node (ref "L13") (pin "2") (pinfunction "2_2") (pintype "passive"))
      (node (ref "T1") (pin "5") (pinfunction "D-3_5") (pintype "bidirectional"))
      (node (ref "T1") (pin "6") (pinfunction "D-2_6") (pintype "bidirectional"))
      (node (ref "T1") (pin "7") (pinfunction "D-1_7") (pintype "bidirectional"))
      (node (ref "T1") (pin "8") (pinfunction "D_8") (pintype "bidirectional"))
      (node (ref "T1") (pin "9") (pinfunction "D_9") (pintype "bidirectional"))
      (node (ref "T2") (pin "1") (pinfunction "S-2_1") (pintype "bidirectional"))
      (node (ref "T2") (pin "2") (pinfunction "S-1_2") (pintype "bidirectional"))
      (node (ref "T2") (pin "3") (pinfunction "S_3") (pintype "bidirectional"))
    )
    (net (code "30") (name "Net-(IC1-SYNCIN{slash}RT)") (class "Default")
      (node (ref "IC1") (pin "8") (pinfunction "SYNCIN/RT_8") (pintype "input"))
      (node (ref "R9") (pin "2") (pinfunction "2_2") (pintype "passive"))
    )
    (net (code "31") (name "Net-(IC1-UVLO)") (class "Default")
      (node (ref "IC1") (pin "6") (pinfunction "UVLO_6") (pintype "input"))
      (node (ref "R6") (pin "1") (pinfunction "1_1") (pintype "passive"))
      (node (ref "R7") (pin "2") (pinfunction "2_2") (pintype "passive"))
      (node (ref "T3") (pin "3") (pinfunction "D_3") (pintype "passive"))
    )
    (net (code "32") (name "Net-(IC1-VCC)") (class "Default")
      (node (ref "C40") (pin "1") (pinfunction "1_1") (pintype "passive"))
      (node (ref "D1") (pin "A") (pinfunction "A_A") (pintype "passive"))
      (node (ref "IC1") (pin "17") (pinfunction "VCC_17") (pintype "power_in"))
    )
    (net (code "33") (name "Net-(IC1-VIN)") (class "Default")
      (node (ref "C39") (pin "2") (pinfunction "2_2") (pintype "passive"))
      (node (ref "IC1") (pin "5") (pinfunction "VIN_5") (pintype "power_in"))
      (node (ref "R5") (pin "1") (pinfunction "1_1") (pintype "passive"))
    )
    (net (code "34") (name "Net-(L13-Pad1)") (class "Default")
      (node (ref "L13") (pin "1") (pinfunction "1_1") (pintype "passive"))
      (node (ref "R1") (pin "2") (pinfunction "2_2") (pintype "passive"))
      (node (ref "R2") (pin "2") (pinfunction "2_2") (pintype "passive"))
      (node (ref "R4") (pin "1") (pinfunction "1_1") (pintype "passive"))
    )
    (net (code "35") (name "Net-(Q1-N-G)") (class "Default")
      (node (ref "Q1") (pin "2") (pinfunction "N-G_2") (pintype "passive"))
      (node (ref "U4") (pin "15") (pinfunction "BGATE_15") (pintype "passive"))
    )
    (net (code "36") (name "Net-(Q1-P-G)") (class "Default")
      (node (ref "Q1") (pin "4") (pinfunction "P-G_4") (pintype "passive"))
      (node (ref "U4") (pin "13") (pinfunction "TGATE_13") (pintype "passive"))
    )
    (net (code "37") (name "Net-(Q2-G)") (class "Default")
      (node (ref "Q2") (pin "4") (pinfunction "G_4") (pintype "passive"))
      (node (ref "U4") (pin "16") (pinfunction "INFET_16") (pintype "input"))
    )
    (net (code "38") (name "Net-(Q2-S)") (class "Default")
      (node (ref "Q2") (pin "5") (pinfunction "S_5") (pintype "passive"))
      (node (ref "R19") (pin "1") (pinfunction "1_1") (pintype "passive"))
      (node (ref "R20") (pin "2") (pinfunction "2_2") (pintype "passive"))
    )
    (net (code "39") (name "Net-(T3-G)") (class "Default")
      (node (ref "R31") (pin "2") (pinfunction "2_2") (pintype "passive"))
      (node (ref "R32") (pin "1") (pinfunction "1_1") (pintype "passive"))
      (node (ref "T3") (pin "1") (pinfunction "G_1") (pintype "passive"))
      (node (ref "T5") (pin "3") (pinfunction "D_3") (pintype "passive"))
    )
    (net (code "40") (name "Net-(T4-D)") (class "Default")
      (node (ref "R11") (pin "1") (pinfunction "1_1") (pintype "passive"))
      (node (ref "R28") (pin "2") (pinfunction "2_2") (pintype "passive"))
      (node (ref "T4") (pin "3") (pinfunction "D_3") (pintype "passive"))
    )
    (net (code "41") (name "Net-(U1-CB)") (class "Default")
      (node (ref "C5") (pin "1") (pinfunction "1_1") (pintype "passive"))
      (node (ref "U1") (pin "1") (pinfunction "CB_1") (pintype "bidirectional"))
    )
    (net (code "42") (name "Net-(U1-FB)") (class "Default")
      (node (ref "R13") (pin "2") (pinfunction "2_2") (pintype "passive"))
      (node (ref "R14") (pin "2") (pinfunction "2_2") (pintype "passive"))
      (node (ref "U1") (pin "3") (pinfunction "FB_3") (pintype "bidirectional"))
    )
    (net (code "43") (name "Net-(U1-SW)") (class "Default")
      (node (ref "C5") (pin "2") (pinfunction "2_2") (pintype "passive"))
      (node (ref "L1") (pin "2") (pinfunction "2_2") (pintype "passive"))
      (node (ref "U1") (pin "6") (pinfunction "SW_6") (pintype "bidirectional"))
    )
    (net (code "44") (name "Net-(U2-CB)") (class "Default")
      (node (ref "C10") (pin "1") (pinfunction "1_1") (pintype "passive"))
      (node (ref "U2") (pin "1") (pinfunction "CB_1") (pintype "bidirectional"))
    )
    (net (code "45") (name "Net-(U2-FB)") (class "Default")
      (node (ref "R15") (pin "2") (pinfunction "2_2") (pintype "passive"))
      (node (ref "R16") (pin "2") (pinfunction "2_2") (pintype "passive"))
      (node (ref "U2") (pin "3") (pinfunction "FB_3") (pintype "bidirectional"))
    )
    (net (code "46") (name "Net-(U2-SW)") (class "Default")
      (node (ref "C10") (pin "2") (pinfunction "2_2") (pintype "passive"))
      (node (ref "L2") (pin "2") (pinfunction "2_2") (pintype "passive"))
      (node (ref "U2") (pin "6") (pinfunction "SW_6") (pintype "bidirectional"))
    )
    (net (code "47") (name "Net-(U3-CB)") (class "Default")
      (node (ref "C15") (pin "1") (pinfunction "1_1") (pintype "passive"))
      (node (ref "U3") (pin "1") (pinfunction "CB_1") (pintype "bidirectional"))
    )
    (net (code "48") (name "Net-(U3-FB)") (class "Default")
      (node (ref "R17") (pin "2") (pinfunction "2_2") (pintype "passive"))
      (node (ref "R18") (pin "2") (pinfunction "2_2") (pintype "passive"))
      (node (ref "U3") (pin "3") (pinfunction "FB_3") (pintype "bidirectional"))
    )
    (net (code "49") (name "Net-(U3-SW)") (class "Default")
      (node (ref "C15") (pin "2") (pinfunction "2_2") (pintype "passive"))
      (node (ref "L3") (pin "2") (pinfunction "2_2") (pintype "passive"))
      (node (ref "U3") (pin "6") (pinfunction "SW_6") (pintype "bidirectional"))
    )
    (net (code "50") (name "Net-(U4-CLP)") (class "Default")
      (node (ref "C17") (pin "1") (pinfunction "1_1") (pintype "passive"))
      (node (ref "R20") (pin "1") (pinfunction "1_1") (pintype "passive"))
      (node (ref "U4") (pin "11") (pinfunction "CLP_11") (pintype "input"))
    )
    (net (code "51") (name "Net-(U4-CSP)") (class "Default")
      (node (ref "L4") (pin "2") (pinfunction "2_2") (pintype "passive"))
      (node (ref "R21") (pin "1") (pinfunction "1_1") (pintype "passive"))
      (node (ref "U4") (pin "9") (pinfunction "CSP_9") (pintype "input"))
    )
    (net (code "52") (name "Net-(U4-ITH)") (class "Default")
      (node (ref "R23") (pin "2") (pinfunction "2_2") (pintype "passive"))
      (node (ref "U4") (pin "7") (pinfunction "ITH_7") (pintype "passive"))
    )
    (net (code "53") (name "Net-(U4-NTC)") (class "Default")
      (node (ref "R24") (pin "1") (pinfunction "1_1") (pintype "passive"))
      (node (ref "U4") (pin "6") (pinfunction "NTC_6") (pintype "passive"))
    )
    (net (code "54") (name "Net-(U4-RT)") (class "Default")
      (node (ref "R22") (pin "2") (pinfunction "2_2") (pintype "passive"))
      (node (ref "U4") (pin "4") (pinfunction "RT_4") (pintype "passive"))
    )
    (net (code "55") (name "VAMP") (class "Default")
      (node (ref "C29") (pin "+") (pinfunction "+_+") (pintype "passive"))
      (node (ref "C44") (pin "+") (pinfunction "+_+") (pintype "passive"))
      (node (ref "C45") (pin "1") (pinfunction "1_1") (pintype "passive"))
      (node (ref "C46") (pin "1") (pinfunction "1_1") (pintype "passive"))
      (node (ref "CN2") (pin "P$6") (pinfunction "6_P$6") (pintype "bidirectional"))
      (node (ref "D3") (pin "C") (pinfunction "C_C") (pintype "passive"))
      (node (ref "D4") (pin "C") (pinfunction "C_C") (pintype "passive"))
      (node (ref "R10") (pin "2") (pinfunction "2_2") (pintype "passive"))
      (node (ref "T2") (pin "5") (pinfunction "D-3_5") (pintype "bidirectional"))
      (node (ref "T2") (pin "6") (pinfunction "D-2_6") (pintype "bidirectional"))
      (node (ref "T2") (pin "7") (pinfunction "D-1_7") (pintype "bidirectional"))
      (node (ref "T2") (pin "8") (pinfunction "D_8") (pintype "bidirectional"))
      (node (ref "T2") (pin "9") (pinfunction "D_9") (pintype "bidirectional"))
    )
    (net (code "56") (name "VBUS") (class "Default")
      (node (ref "C13") (pin "1") (pinfunction "1_1") (pintype "passive"))
      (node (ref "C14") (pin "1") (pinfunction "1_1") (pintype "passive"))
      (node (ref "C17") (pin "2") (pinfunction "2_2") (pintype "passive"))
      (node (ref "C22") (pin "1") (pinfunction "1_1") (pintype "passive"))
      (node (ref "C23") (pin "1") (pinfunction "1_1") (pintype "passive"))
      (node (ref "C3") (pin "1") (pinfunction "1_1") (pintype "passive"))
      (node (ref "C30") (pin "+") (pinfunction "+_+") (pintype "passive"))
      (node (ref "C31") (pin "+") (pinfunction "+_+") (pintype "passive"))
      (node (ref "C4") (pin "1") (pinfunction "1_1") (pintype "passive"))
      (node (ref "C47") (pin "+") (pinfunction "+_+") (pintype "passive"))
      (node (ref "C48") (pin "1") (pinfunction "1_1") (pintype "passive"))
      (node (ref "C51") (pin "1") (pinfunction "1_1") (pintype "passive"))
      (node (ref "C8") (pin "1") (pinfunction "1_1") (pintype "passive"))
      (node (ref "C9") (pin "1") (pinfunction "1_1") (pintype "passive"))
      (node (ref "D3") (pin "A") (pinfunction "A_A") (pintype "passive"))
      (node (ref "D4") (pin "A") (pinfunction "A_A") (pintype "passive"))
      (node (ref "Q1") (pin "3") (pinfunction "P-S_3") (pintype "passive"))
      (node (ref "R1") (pin "1") (pinfunction "1_1") (pintype "passive"))
      (node (ref "R19") (pin "2") (pinfunction "2_2") (pintype "passive"))
      (node (ref "R3") (pin "2") (pinfunction "2_2") (pintype "passive"))
      (node (ref "R32") (pin "2") (pinfunction "2_2") (pintype "passive"))
      (node (ref "R5") (pin "2") (pinfunction "2_2") (pintype "passive"))
      (node (ref "R6") (pin "2") (pinfunction "2_2") (pintype "passive"))
      (node (ref "U1") (pin "5") (pinfunction "VIN_5") (pintype "input"))
      (node (ref "U2") (pin "4") (pinfunction "EN_4") (pintype "bidirectional"))
      (node (ref "U2") (pin "5") (pinfunction "VIN_5") (pintype "input"))
      (node (ref "U3") (pin "5") (pinfunction "VIN_5") (pintype "input"))
      (node (ref "U4") (pin "12") (pinfunction "CLN_12") (pintype "input"))
      (node (ref "VBUS") (pin "1") (pinfunction "P_1") (pintype "passive"))
    )
    (net (code "57") (name "VPIN") (class "Default")
      (node (ref "C16") (pin "1") (pinfunction "1_1") (pintype "passive"))
      (node (ref "C20") (pin "1") (pinfunction "1_1") (pintype "passive"))
      (node (ref "C21") (pin "1") (pinfunction "1_1") (pintype "passive"))
      (node (ref "C24") (pin "+") (pinfunction "+_+") (pintype "passive"))
      (node (ref "Q2") (pin "1") (pinfunction "D_1") (pintype "passive"))
      (node (ref "Q2") (pin "2") (pinfunction "D_2") (pintype "passive"))
      (node (ref "Q2") (pin "3") (pinfunction "D_3") (pintype "passive"))
      (node (ref "Q2") (pin "6") (pinfunction "D_6") (pintype "passive"))
      (node (ref "Q2") (pin "7") (pinfunction "D_7") (pintype "passive"))
      (node (ref "Q2") (pin "8") (pinfunction "D_8") (pintype "passive"))
      (node (ref "R24") (pin "2") (pinfunction "2_2") (pintype "passive"))
      (node (ref "R25") (pin "2") (pinfunction "2_2") (pintype "passive"))
      (node (ref "U4") (pin "1") (pinfunction "DCIN_1") (pintype "input"))
      (node (ref "VPIN") (pin "1") (pinfunction "P_1") (pintype "passive"))
    )
    (net (code "58") (name "unconnected-(IC1-SYNCOUT-Pad1)") (class "Default")
      (node (ref "IC1") (pin "1") (pinfunction "SYNCOUT_1") (pintype "output"))
    )
  )
)
